# obc-v2_CM4-POWER.net
KiCad netlist of a schematic drawn in Altium Designer
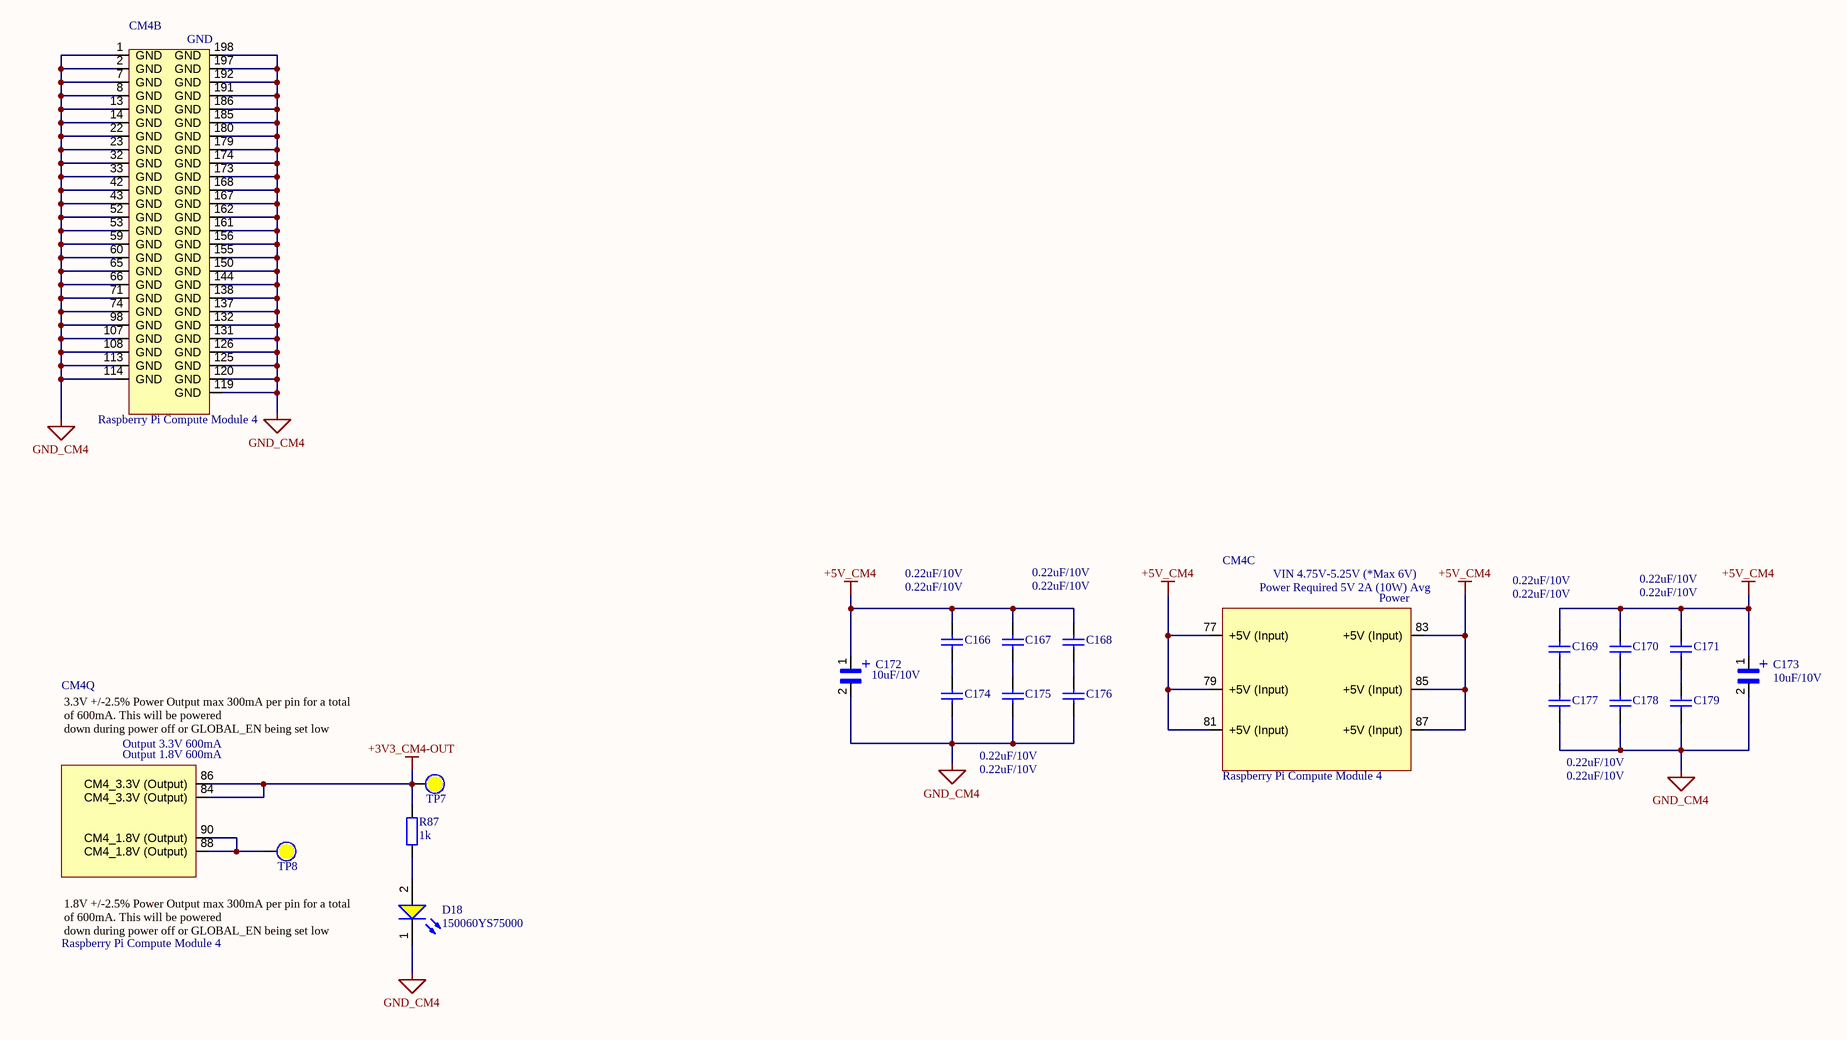
[diagram p0: obc-v2_CM4-POWER.SchDoc]

(export (version "E")
  (design (tool "Eeschema 10.0.6"))
  (components
    (comp (ref "C166")
      (value "0.22uF/10V")
      (footprint "CAP_C_1005X60")
      (description "CAPC")
      (libsource (lib "Altium_Lib_by_KhueNguyenCreator") (part "Tu 0402 33nF 10V"))
    )
    (comp (ref "C167")
      (value "0.22uF/10V")
      (footprint "CAP_C_1005X60")
      (description "CAPC")
      (libsource (lib "Altium_Lib_by_KhueNguyenCreator") (part "Tu 0402 33nF 10V"))
    )
    (comp (ref "C168")
      (value "0.22uF/10V")
      (footprint "CAP_C_1005X60")
      (description "CAPC")
      (libsource (lib "Altium_Lib_by_KhueNguyenCreator") (part "Tu 0402 33nF 10V"))
    )
    (comp (ref "C169")
      (value "0.22uF/10V")
      (footprint "CAP_C_1005X60")
      (description "CAPC")
      (libsource (lib "Altium_Lib_by_KhueNguyenCreator") (part "Tu 0402 33nF 10V"))
    )
    (comp (ref "C170")
      (value "0.22uF/10V")
      (footprint "CAP_C_1005X60")
      (description "CAPC")
      (libsource (lib "Altium_Lib_by_KhueNguyenCreator") (part "Tu 0402 33nF 10V"))
    )
    (comp (ref "C171")
      (value "0.22uF/10V")
      (footprint "CAP_C_1005X60")
      (description "CAPC")
      (libsource (lib "Altium_Lib_by_KhueNguyenCreator") (part "Tu 0402 33nF 10V"))
    )
    (comp (ref "C172")
      (value "10uF/10V")
      (footprint "CAP_MP_2012X170")
      (description "CAPP")
      (fields (field (name "MP") "TACR686M003RTA") (field (name "MF") "AVX"))
      (libsource (lib "TACR686M003RTA") (part "TACR686M003RTA"))
    )
    (comp (ref "C173")
      (value "10uF/10V")
      (footprint "CAP_MP_2012X170")
      (description "CAPP")
      (fields (field (name "MP") "TACR686M003RTA") (field (name "MF") "AVX"))
      (libsource (lib "TACR686M003RTA") (part "TACR686M003RTA"))
    )
    (comp (ref "C174")
      (value "0.22uF/10V")
      (footprint "CAP_C_1005X60")
      (description "CAPC")
      (libsource (lib "Altium_Lib_by_KhueNguyenCreator") (part "Tu 0402 33nF 10V"))
    )
    (comp (ref "C175")
      (value "0.22uF/10V")
      (footprint "CAP_C_1005X60")
      (description "CAPC")
      (libsource (lib "Altium_Lib_by_KhueNguyenCreator") (part "Tu 0402 33nF 10V"))
    )
    (comp (ref "C176")
      (value "0.22uF/10V")
      (footprint "CAP_C_1005X60")
      (description "CAPC")
      (libsource (lib "Altium_Lib_by_KhueNguyenCreator") (part "Tu 0402 33nF 10V"))
    )
    (comp (ref "C177")
      (value "0.22uF/10V")
      (footprint "CAP_C_1005X60")
      (description "CAPC")
      (libsource (lib "Altium_Lib_by_KhueNguyenCreator") (part "Tu 0402 33nF 10V"))
    )
    (comp (ref "C178")
      (value "0.22uF/10V")
      (footprint "CAP_C_1005X60")
      (description "CAPC")
      (libsource (lib "Altium_Lib_by_KhueNguyenCreator") (part "Tu 0402 33nF 10V"))
    )
    (comp (ref "C179")
      (value "0.22uF/10V")
      (footprint "CAP_C_1005X60")
      (description "CAPC")
      (libsource (lib "Altium_Lib_by_KhueNguyenCreator") (part "Tu 0402 33nF 10V"))
    )
    (comp (ref "CM4")
      (value "Raspberry Pi Compute Module 4")
      (footprint "CM4-DF40HC(3.0)-100DS-0.4v_3mm_1.5mm")
      (description "Raspberry Pi Compute Module 4 by Amornthep Phunsin")
      (libsource (lib "CM4") (part "CM4"))
    )
    (comp (ref "D18")
      (value "150060YS75000")
      (footprint "WL-SMCW_0603_150060xx75000")
      (description "LED YELLOW CLEAR 0603 SMD")
      (libsource (lib "Altium Content Vault") (part "LED_Yellow_2A-1K"))
    )
    (comp (ref "R87")
      (value "1k")
      (footprint "RES_C_1608X60")
      (description "RES")
      (libsource (lib "Altium_Lib_by_KhueNguyenCreator") (part "Tro 0603 1% 10k"))
    )
    (comp (ref "TP7")
      (value "~")
      (footprint "Test Point 1 Side")
      (description "Test Point")
      (libsource (lib "BYTECH_HW_LIB_2019 (1)") (part "Test Point"))
    )
    (comp (ref "TP8")
      (value "~")
      (footprint "Test Point 1 Side")
      (description "Test Point")
      (libsource (lib "BYTECH_HW_LIB_2019 (1)") (part "Test Point"))
    )
  )
  (nets
    (net (code "1") (name "+3V3_CM4-OUT") (class "Default")
      (node (ref "CM4") (pin "84") (pinfunction "CM4_3.3V_(Output)_84") (pintype "power_in"))
      (node (ref "CM4") (pin "86") (pinfunction "CM4_3.3V_(Output)_86") (pintype "power_in"))
      (node (ref "R87") (pin "2") (pinfunction "2_2") (pintype "passive"))
      (node (ref "TP7") (pin "0") (pinfunction "0_0") (pintype "passive"))
    )
    (net (code "2") (name "+5V_CM4") (class "Default")
      (node (ref "C166") (pin "1") (pinfunction "1_1") (pintype "passive"))
      (node (ref "C167") (pin "1") (pinfunction "1_1") (pintype "passive"))
      (node (ref "C168") (pin "1") (pinfunction "1_1") (pintype "passive"))
      (node (ref "C169") (pin "1") (pinfunction "1_1") (pintype "passive"))
      (node (ref "C170") (pin "1") (pinfunction "1_1") (pintype "passive"))
      (node (ref "C171") (pin "1") (pinfunction "1_1") (pintype "passive"))
      (node (ref "C172") (pin "1") (pinfunction "1_1") (pintype "passive"))
      (node (ref "C173") (pin "1") (pinfunction "1_1") (pintype "passive"))
      (node (ref "CM4") (pin "77") (pinfunction "+5V_(Input)_77") (pintype "power_in"))
      (node (ref "CM4") (pin "79") (pinfunction "+5V_(Input)_79") (pintype "power_in"))
      (node (ref "CM4") (pin "81") (pinfunction "+5V_(Input)_81") (pintype "power_in"))
      (node (ref "CM4") (pin "83") (pinfunction "+5V_(Input)_83") (pintype "power_in"))
      (node (ref "CM4") (pin "85") (pinfunction "+5V_(Input)_85") (pintype "power_in"))
      (node (ref "CM4") (pin "87") (pinfunction "+5V_(Input)_87") (pintype "power_in"))
    )
    (net (code "3") (name "GND_CM4") (class "Default")
      (node (ref "C172") (pin "2") (pinfunction "2_2") (pintype "passive"))
      (node (ref "C173") (pin "2") (pinfunction "2_2") (pintype "passive"))
      (node (ref "C174") (pin "2") (pinfunction "2_2") (pintype "passive"))
      (node (ref "C175") (pin "2") (pinfunction "2_2") (pintype "passive"))
      (node (ref "C176") (pin "2") (pinfunction "2_2") (pintype "passive"))
      (node (ref "C177") (pin "2") (pinfunction "2_2") (pintype "passive"))
      (node (ref "C178") (pin "2") (pinfunction "2_2") (pintype "passive"))
      (node (ref "C179") (pin "2") (pinfunction "2_2") (pintype "passive"))
      (node (ref "CM4") (pin "1") (pinfunction "GND_1") (pintype "power_in"))
      (node (ref "CM4") (pin "107") (pinfunction "GND_107") (pintype "power_in"))
      (node (ref "CM4") (pin "108") (pinfunction "GND_108") (pintype "power_in"))
      (node (ref "CM4") (pin "113") (pinfunction "GND_113") (pintype "power_in"))
      (node (ref "CM4") (pin "114") (pinfunction "GND_114") (pintype "power_in"))
      (node (ref "CM4") (pin "119") (pinfunction "GND_119") (pintype "power_in"))
      (node (ref "CM4") (pin "120") (pinfunction "GND_120") (pintype "power_in"))
      (node (ref "CM4") (pin "125") (pinfunction "GND_125") (pintype "power_in"))
      (node (ref "CM4") (pin "126") (pinfunction "GND_126") (pintype "power_in"))
      (node (ref "CM4") (pin "13") (pinfunction "GND_13") (pintype "power_in"))
      (node (ref "CM4") (pin "131") (pinfunction "GND_131") (pintype "power_in"))
      (node (ref "CM4") (pin "132") (pinfunction "GND_132") (pintype "power_in"))
      (node (ref "CM4") (pin "137") (pinfunction "GND_137") (pintype "power_in"))
      (node (ref "CM4") (pin "138") (pinfunction "GND_138") (pintype "power_in"))
      (node (ref "CM4") (pin "14") (pinfunction "GND_14") (pintype "power_in"))
      (node (ref "CM4") (pin "144") (pinfunction "GND_144") (pintype "power_in"))
      (node (ref "CM4") (pin "150") (pinfunction "GND_150") (pintype "power_in"))
      (node (ref "CM4") (pin "155") (pinfunction "GND_155") (pintype "power_in"))
      (node (ref "CM4") (pin "156") (pinfunction "GND_156") (pintype "power_in"))
      (node (ref "CM4") (pin "161") (pinfunction "GND_161") (pintype "power_in"))
      (node (ref "CM4") (pin "162") (pinfunction "GND_162") (pintype "power_in"))
      (node (ref "CM4") (pin "167") (pinfunction "GND_167") (pintype "power_in"))
      (node (ref "CM4") (pin "168") (pinfunction "GND_168") (pintype "power_in"))
      (node (ref "CM4") (pin "173") (pinfunction "GND_173") (pintype "power_in"))
      (node (ref "CM4") (pin "174") (pinfunction "GND_174") (pintype "power_in"))
      (node (ref "CM4") (pin "179") (pinfunction "GND_179") (pintype "power_in"))
      (node (ref "CM4") (pin "180") (pinfunction "GND_180") (pintype "power_in"))
      (node (ref "CM4") (pin "185") (pinfunction "GND_185") (pintype "power_in"))
      (node (ref "CM4") (pin "186") (pinfunction "GND_186") (pintype "power_in"))
      (node (ref "CM4") (pin "191") (pinfunction "GND_191") (pintype "power_in"))
      (node (ref "CM4") (pin "192") (pinfunction "GND_192") (pintype "power_in"))
      (node (ref "CM4") (pin "197") (pinfunction "GND_197") (pintype "power_in"))
      (node (ref "CM4") (pin "198") (pinfunction "GND_198") (pintype "power_in"))
      (node (ref "CM4") (pin "2") (pinfunction "GND_2") (pintype "power_in"))
      (node (ref "CM4") (pin "22") (pinfunction "GND_22") (pintype "power_in"))
      (node (ref "CM4") (pin "23") (pinfunction "GND_23") (pintype "power_in"))
      (node (ref "CM4") (pin "32") (pinfunction "GND_32") (pintype "power_in"))
      (node (ref "CM4") (pin "33") (pinfunction "GND_33") (pintype "power_in"))
      (node (ref "CM4") (pin "42") (pinfunction "GND_42") (pintype "power_in"))
      (node (ref "CM4") (pin "43") (pinfunction "GND_43") (pintype "power_in"))
      (node (ref "CM4") (pin "52") (pinfunction "GND_52") (pintype "power_in"))
      (node (ref "CM4") (pin "53") (pinfunction "GND_53") (pintype "power_in"))
      (node (ref "CM4") (pin "59") (pinfunction "GND_59") (pintype "power_in"))
      (node (ref "CM4") (pin "60") (pinfunction "GND_60") (pintype "power_in"))
      (node (ref "CM4") (pin "65") (pinfunction "GND_65") (pintype "power_in"))
      (node (ref "CM4") (pin "66") (pinfunction "GND_66") (pintype "power_in"))
      (node (ref "CM4") (pin "7") (pinfunction "GND_7") (pintype "power_in"))
      (node (ref "CM4") (pin "71") (pinfunction "GND_71") (pintype "power_in"))
      (node (ref "CM4") (pin "74") (pinfunction "GND_74") (pintype "power_in"))
      (node (ref "CM4") (pin "8") (pinfunction "GND_8") (pintype "power_in"))
      (node (ref "CM4") (pin "98") (pinfunction "GND_98") (pintype "power_in"))
      (node (ref "D18") (pin "1") (pinfunction "K_1") (pintype "passive"))
    )
    (net (code "4") (name "Net-(C166-Pad2)") (class "Default")
      (node (ref "C166") (pin "2") (pinfunction "2_2") (pintype "passive"))
      (node (ref "C174") (pin "1") (pinfunction "1_1") (pintype "passive"))
    )
    (net (code "5") (name "Net-(C167-Pad2)") (class "Default")
      (node (ref "C167") (pin "2") (pinfunction "2_2") (pintype "passive"))
      (node (ref "C175") (pin "1") (pinfunction "1_1") (pintype "passive"))
    )
    (net (code "6") (name "Net-(C168-Pad2)") (class "Default")
      (node (ref "C168") (pin "2") (pinfunction "2_2") (pintype "passive"))
      (node (ref "C176") (pin "1") (pinfunction "1_1") (pintype "passive"))
    )
    (net (code "7") (name "Net-(C169-Pad2)") (class "Default")
      (node (ref "C169") (pin "2") (pinfunction "2_2") (pintype "passive"))
      (node (ref "C177") (pin "1") (pinfunction "1_1") (pintype "passive"))
    )
    (net (code "8") (name "Net-(C170-Pad2)") (class "Default")
      (node (ref "C170") (pin "2") (pinfunction "2_2") (pintype "passive"))
      (node (ref "C178") (pin "1") (pinfunction "1_1") (pintype "passive"))
    )
    (net (code "9") (name "Net-(C171-Pad2)") (class "Default")
      (node (ref "C171") (pin "2") (pinfunction "2_2") (pintype "passive"))
      (node (ref "C179") (pin "1") (pinfunction "1_1") (pintype "passive"))
    )
    (net (code "10") (name "Net-(CM4Q-CM4_1.8V_(Output)-Pad88)") (class "Default")
      (node (ref "CM4") (pin "88") (pinfunction "CM4_1.8V_(Output)_88") (pintype "power_in"))
      (node (ref "CM4") (pin "90") (pinfunction "CM4_1.8V_(Output)_90") (pintype "power_in"))
      (node (ref "TP8") (pin "0") (pinfunction "0_0") (pintype "passive"))
    )
    (net (code "11") (name "Net-(D18-A)") (class "Default")
      (node (ref "D18") (pin "2") (pinfunction "A_2") (pintype "passive"))
      (node (ref "R87") (pin "1") (pinfunction "1_1") (pintype "passive"))
    )
  )
)
